# USB_PROGRAMMER.net
KiCad netlist of a schematic drawn in Altium Designer
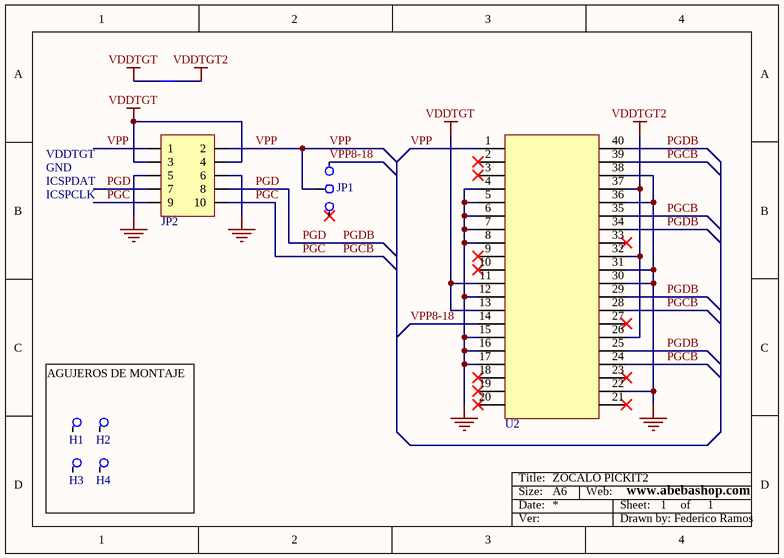
[diagram p0: USB PROGRAMMER.SCHDOC]

(export (version "E")
  (design (tool "Eeschema 10.0.6"))
  (components
    (comp (ref "H1")
      (value "Agujero de montaje")
      (footprint "agujero")
      (libsource (lib "FEDE") (part "Agujero de montaje"))
    )
    (comp (ref "H2")
      (value "Agujero de montaje")
      (footprint "agujero")
      (libsource (lib "FEDE") (part "Agujero de montaje"))
    )
    (comp (ref "H3")
      (value "Agujero de montaje")
      (footprint "agujero")
      (libsource (lib "FEDE") (part "Agujero de montaje"))
    )
    (comp (ref "H4")
      (value "Agujero de montaje")
      (footprint "agujero")
      (libsource (lib "FEDE") (part "Agujero de montaje"))
    )
    (comp (ref "JP1")
      (value "JP2")
      (footprint "hdr3x1")
      (description "Jumper 3 contactos")
      (libsource (lib "FEDE") (part "JP2"))
    )
    (comp (ref "JP2")
      (value "Header5x1")
      (footprint "IDC5x2")
      (description "Header 5x2")
      (libsource (lib "FEDE") (part "Header5x2"))
    )
    (comp (ref "U2")
      (value "SOCKET DIP40")
      (footprint "zif40")
      (description "Socket dip40")
      (libsource (lib "FEDE") (part "SOCKET DIP40"))
    )
    (comp (ref "W9")
      (value "CABLE")
      (footprint "1206NP")
      (description "Cable")
      (libsource (lib "FEDE") (part "CABLE"))
    )
  )
  (nets
    (net (code "1") (name "/PGC") (class "Default")
      (node (ref "JP2") (pin "10") (pinfunction "10_10") (pintype "passive"))
      (node (ref "JP2") (pin "9") (pinfunction "9_9") (pintype "passive"))
      (node (ref "U2") (pin "24") (pinfunction "24_24") (pintype "passive"))
      (node (ref "U2") (pin "28") (pinfunction "28_28") (pintype "passive"))
      (node (ref "U2") (pin "35") (pinfunction "35_35") (pintype "passive"))
      (node (ref "U2") (pin "39") (pinfunction "39_39") (pintype "passive"))
    )
    (net (code "2") (name "/PGD") (class "Default")
      (node (ref "JP2") (pin "7") (pinfunction "7_7") (pintype "passive"))
      (node (ref "JP2") (pin "8") (pinfunction "8_8") (pintype "passive"))
      (node (ref "U2") (pin "25") (pinfunction "25_25") (pintype "passive"))
      (node (ref "U2") (pin "29") (pinfunction "29_29") (pintype "passive"))
      (node (ref "U2") (pin "34") (pinfunction "34_34") (pintype "passive"))
      (node (ref "U2") (pin "40") (pinfunction "40_40") (pintype "passive"))
    )
    (net (code "3") (name "/VPP") (class "Default")
      (node (ref "JP1") (pin "2") (pinfunction "2_2") (pintype "passive"))
      (node (ref "JP2") (pin "1") (pinfunction "1_1") (pintype "passive"))
      (node (ref "JP2") (pin "2") (pinfunction "2_2") (pintype "passive"))
      (node (ref "U2") (pin "1") (pinfunction "1_1") (pintype "passive"))
    )
    (net (code "4") (name "/VPP8-18") (class "Default")
      (node (ref "JP1") (pin "3") (pinfunction "3_3") (pintype "passive"))
      (node (ref "U2") (pin "14") (pinfunction "14_14") (pintype "passive"))
    )
    (net (code "5") (name "GND") (class "Default")
      (node (ref "JP2") (pin "5") (pinfunction "5_5") (pintype "passive"))
      (node (ref "JP2") (pin "6") (pinfunction "6_6") (pintype "passive"))
      (node (ref "U2") (pin "12") (pinfunction "12_12") (pintype "passive"))
      (node (ref "U2") (pin "15") (pinfunction "15_15") (pintype "passive"))
      (node (ref "U2") (pin "16") (pinfunction "16_16") (pintype "passive"))
      (node (ref "U2") (pin "17") (pinfunction "17_17") (pintype "passive"))
      (node (ref "U2") (pin "22") (pinfunction "22_22") (pintype "passive"))
      (node (ref "U2") (pin "30") (pinfunction "30_30") (pintype "passive"))
      (node (ref "U2") (pin "31") (pinfunction "31_31") (pintype "passive"))
      (node (ref "U2") (pin "36") (pinfunction "36_36") (pintype "passive"))
      (node (ref "U2") (pin "38") (pinfunction "38_38") (pintype "passive"))
      (node (ref "U2") (pin "4") (pinfunction "4_4") (pintype "passive"))
      (node (ref "U2") (pin "5") (pinfunction "5_5") (pintype "passive"))
      (node (ref "U2") (pin "6") (pinfunction "6_6") (pintype "passive"))
      (node (ref "U2") (pin "7") (pinfunction "7_7") (pintype "passive"))
      (node (ref "U2") (pin "8") (pinfunction "8_8") (pintype "passive"))
    )
    (net (code "6") (name "VDDTGT") (class "Default")
      (node (ref "JP2") (pin "3") (pinfunction "3_3") (pintype "passive"))
      (node (ref "JP2") (pin "4") (pinfunction "4_4") (pintype "passive"))
      (node (ref "U2") (pin "11") (pinfunction "11_11") (pintype "passive"))
      (node (ref "U2") (pin "13") (pinfunction "13_13") (pintype "passive"))
      (node (ref "W9") (pin "1") (pinfunction "1_1") (pintype "passive"))
    )
    (net (code "7") (name "VDDTGT2") (class "Default")
      (node (ref "U2") (pin "26") (pinfunction "26_26") (pintype "passive"))
      (node (ref "U2") (pin "32") (pinfunction "32_32") (pintype "passive"))
      (node (ref "U2") (pin "37") (pinfunction "37_37") (pintype "passive"))
      (node (ref "W9") (pin "2") (pinfunction "2_2") (pintype "passive"))
    )
    (net (code "8") (name "unconnected-(H1-Pad1)") (class "Default")
      (node (ref "H1") (pin "1") (pinfunction "1_1") (pintype "passive"))
    )
    (net (code "9") (name "unconnected-(H2-Pad1)") (class "Default")
      (node (ref "H2") (pin "1") (pinfunction "1_1") (pintype "passive"))
    )
    (net (code "10") (name "unconnected-(H3-Pad1)") (class "Default")
      (node (ref "H3") (pin "1") (pinfunction "1_1") (pintype "passive"))
    )
    (net (code "11") (name "unconnected-(H4-Pad1)") (class "Default")
      (node (ref "H4") (pin "1") (pinfunction "1_1") (pintype "passive"))
    )
    (net (code "12") (name "unconnected-(JP1-Pad1)") (class "Default")
      (node (ref "JP1") (pin "1") (pinfunction "1_1") (pintype "passive+no_connect"))
    )
    (net (code "13") (name "unconnected-(U2-Pad2)") (class "Default")
      (node (ref "U2") (pin "2") (pinfunction "2_2") (pintype "passive+no_connect"))
    )
    (net (code "14") (name "unconnected-(U2-Pad3)") (class "Default")
      (node (ref "U2") (pin "3") (pinfunction "3_3") (pintype "passive+no_connect"))
    )
    (net (code "15") (name "unconnected-(U2-Pad9)") (class "Default")
      (node (ref "U2") (pin "9") (pinfunction "9_9") (pintype "passive+no_connect"))
    )
    (net (code "16") (name "unconnected-(U2-Pad10)") (class "Default")
      (node (ref "U2") (pin "10") (pinfunction "10_10") (pintype "passive+no_connect"))
    )
    (net (code "17") (name "unconnected-(U2-Pad18)") (class "Default")
      (node (ref "U2") (pin "18") (pinfunction "18_18") (pintype "passive+no_connect"))
    )
    (net (code "18") (name "unconnected-(U2-Pad19)") (class "Default")
      (node (ref "U2") (pin "19") (pinfunction "19_19") (pintype "passive+no_connect"))
    )
    (net (code "19") (name "unconnected-(U2-Pad20)") (class "Default")
      (node (ref "U2") (pin "20") (pinfunction "20_20") (pintype "passive+no_connect"))
    )
    (net (code "20") (name "unconnected-(U2-Pad21)") (class "Default")
      (node (ref "U2") (pin "21") (pinfunction "21_21") (pintype "passive+no_connect"))
    )
    (net (code "21") (name "unconnected-(U2-Pad23)") (class "Default")
      (node (ref "U2") (pin "23") (pinfunction "23_23") (pintype "passive+no_connect"))
    )
    (net (code "22") (name "unconnected-(U2-Pad27)") (class "Default")
      (node (ref "U2") (pin "27") (pinfunction "27_27") (pintype "passive+no_connect"))
    )
    (net (code "23") (name "unconnected-(U2-Pad33)") (class "Default")
      (node (ref "U2") (pin "33") (pinfunction "33_33") (pintype "passive+no_connect"))
    )
  )
)
